# EIS_Main_SensorInterface.net
KiCad netlist of a schematic drawn in Altium Designer
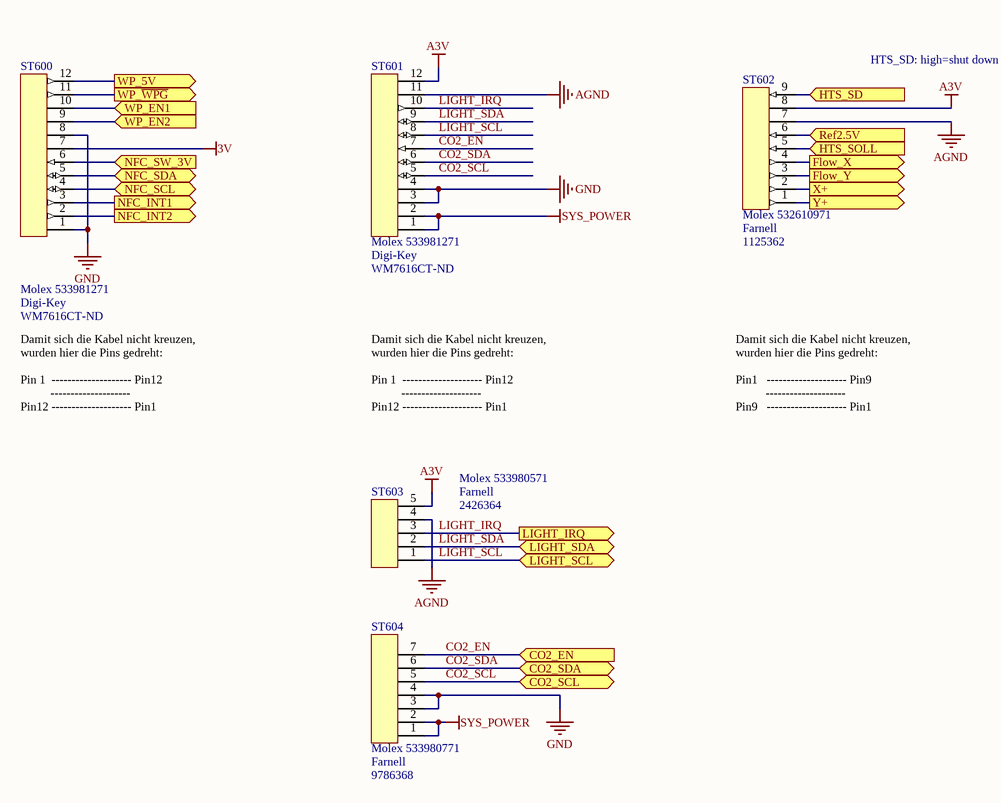
[diagram p0: EIS_Main_SensorInterface.SchDoc]

(export (version "E")
  (design (tool "Eeschema 10.0.6"))
  (components
    (comp (ref "ST600")
      (value "Molex 533981271")
      (footprint "Molex 533981271")
      (description "Molex Pico 12Pol Blade SMD gerade 533980871")
      (fields (field (name "SUPPLIER 1") "Digi-Key") (field (name "SUPPLIER PART NUMBER 1") "WM7616CT-ND"))
      (libsource (lib "JM_Elektromechanik") (part "Molex 533981271"))
    )
    (comp (ref "ST601")
      (value "Molex 533981271")
      (footprint "Molex 533981271")
      (description "Molex Pico 12Pol Blade SMD gerade 533980871")
      (fields (field (name "SUPPLIER 1") "Digi-Key") (field (name "SUPPLIER PART NUMBER 1") "WM7616CT-ND"))
      (libsource (lib "JM_Elektromechanik") (part "Molex 533981271"))
    )
    (comp (ref "ST602")
      (value "Molex 532610971")
      (footprint "Molex 532610971")
      (description "Stecker 9Pol universal")
      (fields (field (name "SUPPLIER 1") "Farnell") (field (name "SUPPLIER PART NUMBER 1") "1125362"))
      (libsource (lib "JM_Elektromechanik") (part "Molex 532610971"))
    )
    (comp (ref "ST603")
      (value "Molex 533980571")
      (footprint "Molex 533980571")
      (description "MOLEX - 53398-0571 - STIFTLEISTE, SMT, 1.25MM, 5POL")
      (fields (field (name "SUPPLIER 1") "Farnell") (field (name "SUPPLIER PART NUMBER 1") "2426364"))
      (libsource (lib "JM_Elektromechanik") (part "Molex 533980571"))
    )
    (comp (ref "ST604")
      (value "Molex 533980771")
      (footprint "Molex 533980771")
      (description "Molex Pico 7Pol Blade SMD gerade 533980771")
      (fields (field (name "SUPPLIER 2") "Farnell") (field (name "SUPPLIER PART NUMBER 2") "9786368"))
      (libsource (lib "JM_Elektromechanik") (part "Molex 533980771"))
    )
  )
  (nets
    (net (code "1") (name "/CO2_EN") (class "Default")
      (node (ref "ST601") (pin "7") (pinfunction "7_7") (pintype "passive"))
      (node (ref "ST604") (pin "7") (pinfunction "7_7") (pintype "passive"))
    )
    (net (code "2") (name "/CO2_SCL") (class "Default")
      (node (ref "ST601") (pin "5") (pinfunction "5_5") (pintype "bidirectional"))
      (node (ref "ST604") (pin "5") (pinfunction "5_5") (pintype "passive"))
    )
    (net (code "3") (name "/CO2_SDA") (class "Default")
      (node (ref "ST601") (pin "6") (pinfunction "6_6") (pintype "input"))
      (node (ref "ST604") (pin "6") (pinfunction "6_6") (pintype "passive"))
    )
    (net (code "4") (name "/Flow_X") (class "Default")
      (node (ref "ST602") (pin "4") (pinfunction "4_4") (pintype "output"))
    )
    (net (code "5") (name "/Flow_Y") (class "Default")
      (node (ref "ST602") (pin "3") (pinfunction "3_3") (pintype "output"))
    )
    (net (code "6") (name "/HTS_SD") (class "Default")
      (node (ref "ST602") (pin "9") (pinfunction "9_9") (pintype "input"))
    )
    (net (code "7") (name "/HTS_SOLL") (class "Default")
      (node (ref "ST602") (pin "5") (pinfunction "5_5") (pintype "input"))
    )
    (net (code "8") (name "/LIGHT_IRQ") (class "Default")
      (node (ref "ST601") (pin "10") (pinfunction "10_10") (pintype "passive"))
      (node (ref "ST603") (pin "3") (pinfunction "3_3") (pintype "passive"))
    )
    (net (code "9") (name "/LIGHT_SCL") (class "Default")
      (node (ref "ST601") (pin "8") (pinfunction "8_8") (pintype "passive"))
      (node (ref "ST603") (pin "1") (pinfunction "1_1") (pintype "passive"))
    )
    (net (code "10") (name "/LIGHT_SDA") (class "Default")
      (node (ref "ST601") (pin "9") (pinfunction "9_9") (pintype "passive"))
      (node (ref "ST603") (pin "2") (pinfunction "2_2") (pintype "passive"))
    )
    (net (code "11") (name "/NFC_INT1") (class "Default")
      (node (ref "ST600") (pin "3") (pinfunction "3_3") (pintype "output"))
    )
    (net (code "12") (name "/NFC_INT2") (class "Default")
      (node (ref "ST600") (pin "2") (pinfunction "2_2") (pintype "output"))
    )
    (net (code "13") (name "/NFC_SCL") (class "Default")
      (node (ref "ST600") (pin "4") (pinfunction "4_4") (pintype "bidirectional"))
    )
    (net (code "14") (name "/NFC_SDA") (class "Default")
      (node (ref "ST600") (pin "5") (pinfunction "5_5") (pintype "bidirectional"))
    )
    (net (code "15") (name "/NFC_SW_3V") (class "Default")
      (node (ref "ST600") (pin "6") (pinfunction "6_6") (pintype "input"))
    )
    (net (code "16") (name "/Ref2.5V") (class "Default")
      (node (ref "ST602") (pin "6") (pinfunction "6_6") (pintype "input"))
    )
    (net (code "17") (name "/WP_5V") (class "Default")
      (node (ref "ST600") (pin "12") (pinfunction "12_12") (pintype "output"))
    )
    (net (code "18") (name "/WP_EN1") (class "Default")
      (node (ref "ST600") (pin "10") (pinfunction "10_10") (pintype "passive"))
    )
    (net (code "19") (name "/WP_EN2") (class "Default")
      (node (ref "ST600") (pin "9") (pinfunction "9_9") (pintype "passive"))
    )
    (net (code "20") (name "/WP_~{WPG}") (class "Default")
      (node (ref "ST600") (pin "11") (pinfunction "11_11") (pintype "output"))
    )
    (net (code "21") (name "/X+") (class "Default")
      (node (ref "ST602") (pin "2") (pinfunction "2_2") (pintype "output"))
    )
    (net (code "22") (name "/Y+") (class "Default")
      (node (ref "ST602") (pin "1") (pinfunction "1_1") (pintype "output"))
    )
    (net (code "23") (name "3V") (class "Default")
      (node (ref "ST600") (pin "7") (pinfunction "7_7") (pintype "passive"))
    )
    (net (code "24") (name "A3V") (class "Default")
      (node (ref "ST601") (pin "12") (pinfunction "12_12") (pintype "output"))
      (node (ref "ST602") (pin "8") (pinfunction "8_8") (pintype "passive"))
      (node (ref "ST603") (pin "5") (pinfunction "5_5") (pintype "passive"))
    )
    (net (code "25") (name "AGND") (class "Default")
      (node (ref "ST601") (pin "11") (pinfunction "11_11") (pintype "output"))
      (node (ref "ST602") (pin "7") (pinfunction "7_7") (pintype "passive"))
      (node (ref "ST603") (pin "4") (pinfunction "4_4") (pintype "passive"))
    )
    (net (code "26") (name "GND") (class "Default")
      (node (ref "ST600") (pin "1") (pinfunction "1_1") (pintype "passive"))
      (node (ref "ST600") (pin "8") (pinfunction "8_8") (pintype "passive"))
      (node (ref "ST601") (pin "3") (pinfunction "3_3") (pintype "output"))
      (node (ref "ST601") (pin "4") (pinfunction "4_4") (pintype "bidirectional"))
      (node (ref "ST604") (pin "3") (pinfunction "3_3") (pintype "passive"))
      (node (ref "ST604") (pin "4") (pinfunction "4_4") (pintype "passive"))
    )
    (net (code "27") (name "SYS_POWER") (class "Default")
      (node (ref "ST601") (pin "1") (pinfunction "1_1") (pintype "passive"))
      (node (ref "ST601") (pin "2") (pinfunction "2_2") (pintype "output"))
      (node (ref "ST604") (pin "1") (pinfunction "1_1") (pintype "passive"))
      (node (ref "ST604") (pin "2") (pinfunction "2_2") (pintype "passive"))
    )
    (net (code "28") (name "unconnected-(ST600-Pad13)") (class "Default")
      (node (ref "ST600") (pin "13") (pinfunction "13_13") (pintype "passive"))
    )
    (net (code "29") (name "unconnected-(ST600-Pad14)") (class "Default")
      (node (ref "ST600") (pin "14") (pinfunction "14_14") (pintype "passive"))
    )
    (net (code "30") (name "unconnected-(ST601-Pad13)") (class "Default")
      (node (ref "ST601") (pin "13") (pinfunction "13_13") (pintype "passive"))
    )
    (net (code "31") (name "unconnected-(ST601-Pad14)") (class "Default")
      (node (ref "ST601") (pin "14") (pinfunction "14_14") (pintype "passive"))
    )
    (net (code "32") (name "unconnected-(ST603-Pad6)") (class "Default")
      (node (ref "ST603") (pin "6") (pinfunction "6_6") (pintype "passive"))
    )
    (net (code "33") (name "unconnected-(ST603-Pad7)") (class "Default")
      (node (ref "ST603") (pin "7") (pinfunction "7_7") (pintype "passive"))
    )
    (net (code "34") (name "unconnected-(ST604-Pad8)") (class "Default")
      (node (ref "ST604") (pin "8") (pinfunction "8_8") (pintype "passive"))
    )
    (net (code "35") (name "unconnected-(ST604-Pad9)") (class "Default")
      (node (ref "ST604") (pin "9") (pinfunction "9_9") (pintype "passive"))
    )
  )
)
